# SparkFun_RTK_Facet_-_Display_SD_SIM.net
KiCad netlist of a schematic drawn in EAGLE
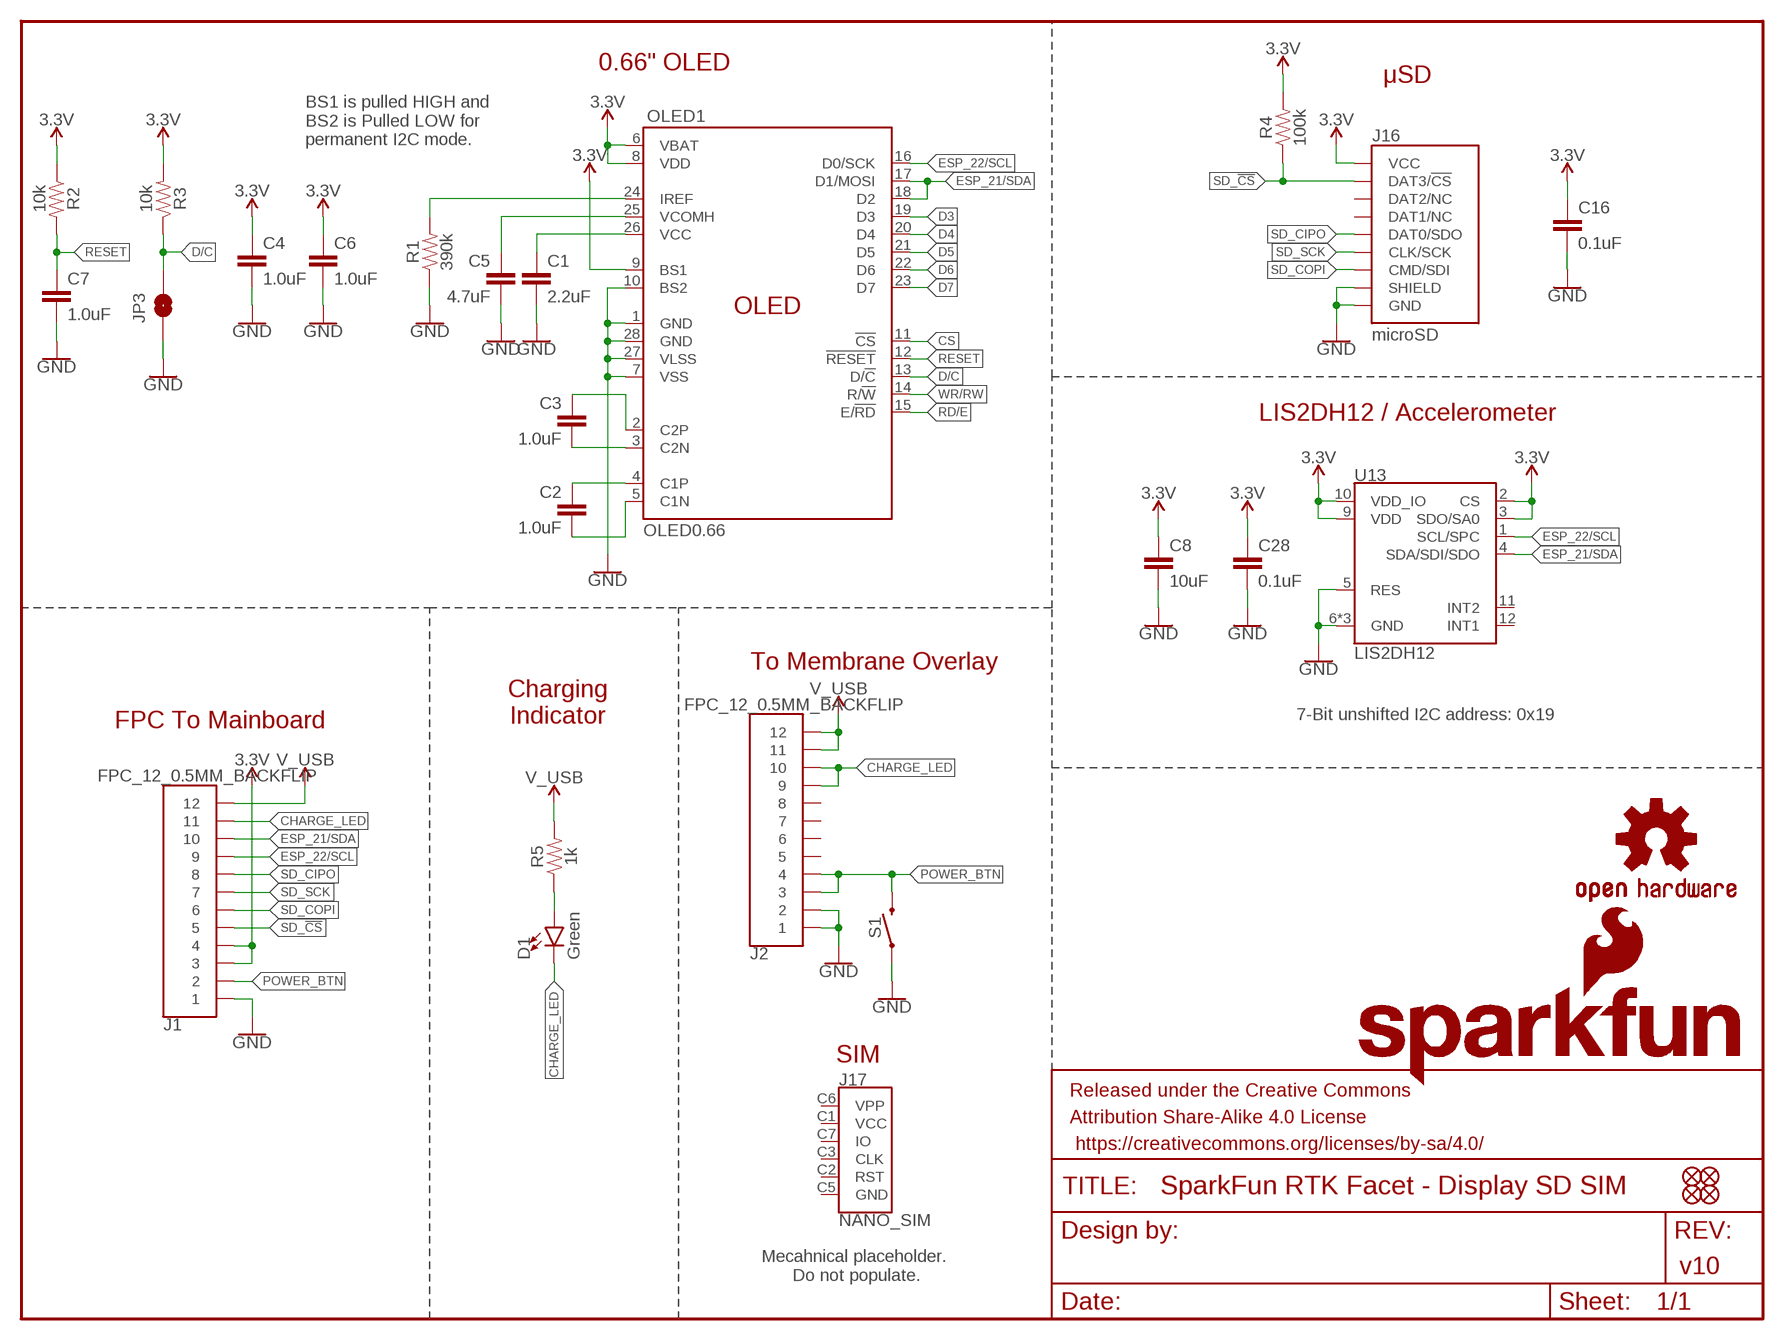
[diagram p0: schematic, sheet 1]

(export (version "E")
  (design (tool "Eeschema 10.0.6"))
  (components
    (comp (ref "C1")
      (value "2.2uF")
      (footprint "eagle-import:0805")
      (libsource (lib "eagle-import") (part "2.2UF-0805-25V-(+80/-20%)"))
    )
    (comp (ref "C2")
      (value "1.0uF")
      (footprint "eagle-import:0805")
      (libsource (lib "eagle-import") (part "1.0UF-0805-25V-10%"))
    )
    (comp (ref "C3")
      (value "1.0uF")
      (footprint "eagle-import:0805")
      (libsource (lib "eagle-import") (part "1.0UF-0805-25V-10%"))
    )
    (comp (ref "C4")
      (value "1.0uF")
      (footprint "eagle-import:0603")
      (libsource (lib "eagle-import") (part "1.0UF-0603-16V-10%"))
    )
    (comp (ref "C5")
      (value "4.7uF")
      (footprint "eagle-import:1206")
      (libsource (lib "eagle-import") (part "4.7UF-1206-16V-(+80/-20%)"))
    )
    (comp (ref "C6")
      (value "1.0uF")
      (footprint "eagle-import:0603")
      (libsource (lib "eagle-import") (part "1.0UF-0603-16V-10%"))
    )
    (comp (ref "C7")
      (value "1.0uF")
      (footprint "eagle-import:0603")
      (libsource (lib "eagle-import") (part "1.0UF-0603-16V-10%"))
    )
    (comp (ref "C8")
      (value "10uF")
      (footprint "eagle-import:0603")
      (libsource (lib "eagle-import") (part "10UF-0603-6.3V-20%"))
    )
    (comp (ref "C16")
      (value "0.1uF")
      (footprint "eagle-import:0603")
      (libsource (lib "eagle-import") (part "0.1UF-0603-25V-(+80/-20%)"))
    )
    (comp (ref "C28")
      (value "0.1uF")
      (footprint "eagle-import:0603")
      (libsource (lib "eagle-import") (part "0.1UF-0603-25V-(+80/-20%)"))
    )
    (comp (ref "D1")
      (value "Green")
      (footprint "eagle-import:LED-1206-BOTTOM")
      (libsource (lib "eagle-import") (part "LED-GREEN1206-BOTTOM"))
    )
    (comp (ref "FID1")
      (value "FIDUCIAL1X2")
      (footprint "eagle-import:FIDUCIAL-1X2")
      (libsource (lib "eagle-import") (part "FIDUCIAL1X2"))
    )
    (comp (ref "FID2")
      (value "FIDUCIAL1X2")
      (footprint "eagle-import:FIDUCIAL-1X2")
      (libsource (lib "eagle-import") (part "FIDUCIAL1X2"))
    )
    (comp (ref "FID3")
      (value "FIDUCIAL1X2")
      (footprint "eagle-import:FIDUCIAL-1X2")
      (libsource (lib "eagle-import") (part "FIDUCIAL1X2"))
    )
    (comp (ref "FID4")
      (value "FIDUCIAL1X2")
      (footprint "eagle-import:FIDUCIAL-1X2")
      (libsource (lib "eagle-import") (part "FIDUCIAL1X2"))
    )
    (comp (ref "FRAME1")
      (value "FRAME-LETTER")
      (footprint "eagle-import:CREATIVE_COMMONS")
      (libsource (lib "eagle-import") (part "FRAME-LETTER"))
    )
    (comp (ref "J1")
      (value "FPC_12_0.5MM_BACKFLIP")
      (footprint "eagle-import:FPC_12_DOUBLESIDED_BACKFLIP")
      (libsource (lib "eagle-import") (part "FPC_12_0.5MM_BACKFLIP"))
    )
    (comp (ref "J2")
      (value "FPC_12_0.5MM_BACKFLIP")
      (footprint "eagle-import:FPC_12_DOUBLESIDED_BACKFLIP")
      (libsource (lib "eagle-import") (part "FPC_12_0.5MM_BACKFLIP"))
    )
    (comp (ref "J16")
      (value "microSD")
      (footprint "eagle-import:MICRO-SD-SOCKET")
      (libsource (lib "eagle-import") (part "MICRO-SD-SDIOPUSH-PUSH"))
    )
    (comp (ref "J17")
      (value "NANO_SIM")
      (footprint "eagle-import:NANO_SIM_WURTH_693043020611")
      (libsource (lib "eagle-import") (part "NANO_SIMWURTH"))
    )
    (comp (ref "JP3")
      (value "JUMPER-SMT_2_NO_SILK")
      (footprint "eagle-import:SMT-JUMPER_2_NO_SILK")
      (libsource (lib "eagle-import") (part "JUMPER-SMT_2_NO_SILK"))
    )
    (comp (ref "LOGO3")
      (value "OSHW-LOGOMINI")
      (footprint "eagle-import:OSHW-LOGO-MINI")
      (libsource (lib "eagle-import") (part "OSHW-LOGOMINI"))
    )
    (comp (ref "LOGO5")
      (value "SFE_LOGO_NAME_FLAME.1_INCH")
      (footprint "eagle-import:SFE_LOGO_NAME_FLAME_.1")
      (libsource (lib "eagle-import") (part "SFE_LOGO_NAME_FLAME.1_INCH"))
    )
    (comp (ref "OLED1")
      (value "OLED0.66")
      (footprint "eagle-import:OLED-0.66-64X48")
      (libsource (lib "eagle-import") (part "OLED0.66"))
    )
    (comp (ref "R1")
      (value "390k")
      (footprint "eagle-import:0603")
      (libsource (lib "eagle-import") (part "390KOHM-0603-1/10W-1%"))
    )
    (comp (ref "R2")
      (value "10k")
      (footprint "eagle-import:0603")
      (libsource (lib "eagle-import") (part "10KOHM-0603-1/10W-1%"))
    )
    (comp (ref "R3")
      (value "10k")
      (footprint "eagle-import:0603")
      (libsource (lib "eagle-import") (part "10KOHM-0603-1/10W-1%"))
    )
    (comp (ref "R4")
      (value "100k")
      (footprint "eagle-import:0603")
      (libsource (lib "eagle-import") (part "100KOHM-0603-1/10W-1%"))
    )
    (comp (ref "R5")
      (value "1k")
      (footprint "eagle-import:0603")
      (libsource (lib "eagle-import") (part "1KOHM-0603-1/10W-1%"))
    )
    (comp (ref "S1")
      (value "MOMENTARY-SWITCH-SPST-SMD-5.2MM-TALL")
      (footprint "eagle-import:TACTILE_SWITCH_SMD_5.2MM")
      (libsource (lib "eagle-import") (part "MOMENTARY-SWITCH-SPST-SMD-5.2MM-TALL"))
    )
    (comp (ref "U13")
      (value "LIS2DH12")
      (footprint "eagle-import:LGA-12-LISDH12")
      (libsource (lib "eagle-import") (part "LIS2DH12"))
    )
  )
  (nets
    (net (code "1") (name "/SD_~{CS}") (class "Default")
      (node (ref "J1") (pin "5") (pinfunction "5_5") (pintype "bidirectional"))
      (node (ref "J16") (pin "CS/DAT3") (pinfunction "DAT3/~{CS}_CS/DAT3") (pintype "bidirectional"))
      (node (ref "R4") (pin "1") (pinfunction "1_1") (pintype "passive"))
    )
    (net (code "2") (name "3.3V") (class "Default")
      (node (ref "C16") (pin "1") (pinfunction "1_1") (pintype "passive"))
      (node (ref "C28") (pin "1") (pinfunction "1_1") (pintype "passive"))
      (node (ref "C4") (pin "1") (pinfunction "1_1") (pintype "passive"))
      (node (ref "C6") (pin "1") (pinfunction "1_1") (pintype "passive"))
      (node (ref "C8") (pin "1") (pinfunction "1_1") (pintype "passive"))
      (node (ref "J1") (pin "3") (pinfunction "3_3") (pintype "bidirectional"))
      (node (ref "J1") (pin "4") (pinfunction "4_4") (pintype "bidirectional"))
      (node (ref "J16") (pin "VCC") (pinfunction "VCC_VCC") (pintype "bidirectional"))
      (node (ref "OLED1") (pin "6") (pinfunction "VBAT_6") (pintype "bidirectional"))
      (node (ref "OLED1") (pin "8") (pinfunction "VDD_8") (pintype "bidirectional"))
      (node (ref "OLED1") (pin "9") (pinfunction "BS1_9") (pintype "bidirectional"))
      (node (ref "R2") (pin "1") (pinfunction "1_1") (pintype "passive"))
      (node (ref "R3") (pin "2") (pinfunction "2_2") (pintype "passive"))
      (node (ref "R4") (pin "2") (pinfunction "2_2") (pintype "passive"))
      (node (ref "U13") (pin "10") (pinfunction "VDD_IO_10") (pintype "bidirectional"))
      (node (ref "U13") (pin "2") (pinfunction "CS_2") (pintype "bidirectional"))
      (node (ref "U13") (pin "3") (pinfunction "SDO/SA0_3") (pintype "bidirectional"))
      (node (ref "U13") (pin "9") (pinfunction "VDD_9") (pintype "bidirectional"))
    )
    (net (code "3") (name "CHARGE_LED") (class "Default")
      (node (ref "D1") (pin "C") (pinfunction "C_C") (pintype "passive"))
      (node (ref "J1") (pin "11") (pinfunction "11_11") (pintype "bidirectional"))
      (node (ref "J2") (pin "10") (pinfunction "10_10") (pintype "bidirectional"))
      (node (ref "J2") (pin "9") (pinfunction "9_9") (pintype "bidirectional"))
    )
    (net (code "4") (name "CS") (class "Default")
      (node (ref "OLED1") (pin "11") (pinfunction "~{CS}_11") (pintype "bidirectional"))
    )
    (net (code "5") (name "D3") (class "Default")
      (node (ref "OLED1") (pin "19") (pinfunction "D3_19") (pintype "bidirectional"))
    )
    (net (code "6") (name "D4") (class "Default")
      (node (ref "OLED1") (pin "20") (pinfunction "D4_20") (pintype "bidirectional"))
    )
    (net (code "7") (name "D5") (class "Default")
      (node (ref "OLED1") (pin "21") (pinfunction "D5_21") (pintype "bidirectional"))
    )
    (net (code "8") (name "D6") (class "Default")
      (node (ref "OLED1") (pin "22") (pinfunction "D6_22") (pintype "bidirectional"))
    )
    (net (code "9") (name "D7") (class "Default")
      (node (ref "OLED1") (pin "23") (pinfunction "D7_23") (pintype "bidirectional"))
    )
    (net (code "10") (name "D{slash}C") (class "Default")
      (node (ref "JP3") (pin "2") (pinfunction "2_2") (pintype "passive"))
      (node (ref "OLED1") (pin "13") (pinfunction "D/~{C}_13") (pintype "bidirectional"))
      (node (ref "R3") (pin "1") (pinfunction "1_1") (pintype "passive"))
    )
    (net (code "11") (name "ESP_21{slash}SDA") (class "Default")
      (node (ref "J1") (pin "10") (pinfunction "10_10") (pintype "bidirectional"))
      (node (ref "OLED1") (pin "17") (pinfunction "D1/MOSI_17") (pintype "bidirectional"))
      (node (ref "OLED1") (pin "18") (pinfunction "D2_18") (pintype "bidirectional"))
      (node (ref "U13") (pin "4") (pinfunction "SDA/SDI/SDO_4") (pintype "bidirectional"))
    )
    (net (code "12") (name "ESP_22{slash}SCL") (class "Default")
      (node (ref "J1") (pin "9") (pinfunction "9_9") (pintype "bidirectional"))
      (node (ref "OLED1") (pin "16") (pinfunction "D0/SCK_16") (pintype "bidirectional"))
      (node (ref "U13") (pin "1") (pinfunction "SCL/SPC_1") (pintype "bidirectional"))
    )
    (net (code "13") (name "GND") (class "Default")
      (node (ref "C1") (pin "2") (pinfunction "2_2") (pintype "passive"))
      (node (ref "C16") (pin "2") (pinfunction "2_2") (pintype "passive"))
      (node (ref "C28") (pin "2") (pinfunction "2_2") (pintype "passive"))
      (node (ref "C4") (pin "2") (pinfunction "2_2") (pintype "passive"))
      (node (ref "C5") (pin "2") (pinfunction "2_2") (pintype "passive"))
      (node (ref "C6") (pin "2") (pinfunction "2_2") (pintype "passive"))
      (node (ref "C7") (pin "2") (pinfunction "2_2") (pintype "passive"))
      (node (ref "C8") (pin "2") (pinfunction "2_2") (pintype "passive"))
      (node (ref "J1") (pin "1") (pinfunction "1_1") (pintype "bidirectional"))
      (node (ref "J16") (pin "CD1") (pinfunction "SHIELD_CD1") (pintype "bidirectional"))
      (node (ref "J16") (pin "GND") (pinfunction "GND_GND") (pintype "bidirectional"))
      (node (ref "J16") (pin "GND1") (pinfunction "GND_GND1") (pintype "bidirectional"))
      (node (ref "J16") (pin "GND3") (pinfunction "GND_GND3") (pintype "bidirectional"))
      (node (ref "J2") (pin "1") (pinfunction "1_1") (pintype "bidirectional"))
      (node (ref "J2") (pin "2") (pinfunction "2_2") (pintype "bidirectional"))
      (node (ref "JP3") (pin "1") (pinfunction "1_1") (pintype "passive"))
      (node (ref "OLED1") (pin "1") (pinfunction "GND_1") (pintype "bidirectional"))
      (node (ref "OLED1") (pin "10") (pinfunction "BS2_10") (pintype "bidirectional"))
      (node (ref "OLED1") (pin "27") (pinfunction "VLSS_27") (pintype "bidirectional"))
      (node (ref "OLED1") (pin "28") (pinfunction "GND_28") (pintype "bidirectional"))
      (node (ref "OLED1") (pin "7") (pinfunction "VSS_7") (pintype "bidirectional"))
      (node (ref "R1") (pin "1") (pinfunction "1_1") (pintype "passive"))
      (node (ref "S1") (pin "1") (pinfunction "1_1") (pintype "passive"))
      (node (ref "U13") (pin "5") (pinfunction "RES_5") (pintype "bidirectional"))
      (node (ref "U13") (pin "6") (pinfunction "GND_6") (pintype "bidirectional"))
      (node (ref "U13") (pin "7") (pinfunction "GND_7") (pintype "bidirectional"))
      (node (ref "U13") (pin "8") (pinfunction "GND_8") (pintype "bidirectional"))
    )
    (net (code "14") (name "Net-(D1-PadA)") (class "Default")
      (node (ref "D1") (pin "A") (pinfunction "A_A") (pintype "passive"))
      (node (ref "R5") (pin "1") (pinfunction "1_1") (pintype "passive"))
    )
    (net (code "15") (name "Net-(OLED1-C1N)") (class "Default")
      (node (ref "C2") (pin "2") (pinfunction "2_2") (pintype "passive"))
      (node (ref "OLED1") (pin "5") (pinfunction "C1N_5") (pintype "bidirectional"))
    )
    (net (code "16") (name "Net-(OLED1-C1P)") (class "Default")
      (node (ref "C2") (pin "1") (pinfunction "1_1") (pintype "passive"))
      (node (ref "OLED1") (pin "4") (pinfunction "C1P_4") (pintype "bidirectional"))
    )
    (net (code "17") (name "Net-(OLED1-C2N)") (class "Default")
      (node (ref "C3") (pin "2") (pinfunction "2_2") (pintype "passive"))
      (node (ref "OLED1") (pin "3") (pinfunction "C2N_3") (pintype "bidirectional"))
    )
    (net (code "18") (name "Net-(OLED1-C2P)") (class "Default")
      (node (ref "C3") (pin "1") (pinfunction "1_1") (pintype "passive"))
      (node (ref "OLED1") (pin "2") (pinfunction "C2P_2") (pintype "bidirectional"))
    )
    (net (code "19") (name "Net-(OLED1-IREF)") (class "Default")
      (node (ref "OLED1") (pin "24") (pinfunction "IREF_24") (pintype "bidirectional"))
      (node (ref "R1") (pin "2") (pinfunction "2_2") (pintype "passive"))
    )
    (net (code "20") (name "Net-(OLED1-VCC)") (class "Default")
      (node (ref "C1") (pin "1") (pinfunction "1_1") (pintype "passive"))
      (node (ref "OLED1") (pin "26") (pinfunction "VCC_26") (pintype "bidirectional"))
    )
    (net (code "21") (name "Net-(OLED1-VCOMH)") (class "Default")
      (node (ref "C5") (pin "1") (pinfunction "1_1") (pintype "passive"))
      (node (ref "OLED1") (pin "25") (pinfunction "VCOMH_25") (pintype "bidirectional"))
    )
    (net (code "22") (name "POWER_BTN") (class "Default")
      (node (ref "J1") (pin "2") (pinfunction "2_2") (pintype "bidirectional"))
      (node (ref "J2") (pin "3") (pinfunction "3_3") (pintype "bidirectional"))
      (node (ref "J2") (pin "4") (pinfunction "4_4") (pintype "bidirectional"))
      (node (ref "S1") (pin "3") (pinfunction "2_3") (pintype "passive"))
    )
    (net (code "23") (name "RD{slash}E") (class "Default")
      (node (ref "OLED1") (pin "15") (pinfunction "E/~{RD}_15") (pintype "bidirectional"))
    )
    (net (code "24") (name "RESET") (class "Default")
      (node (ref "C7") (pin "1") (pinfunction "1_1") (pintype "passive"))
      (node (ref "OLED1") (pin "12") (pinfunction "~{RESET}_12") (pintype "bidirectional"))
      (node (ref "R2") (pin "2") (pinfunction "2_2") (pintype "passive"))
    )
    (net (code "25") (name "SD_CIPO") (class "Default")
      (node (ref "J1") (pin "8") (pinfunction "8_8") (pintype "bidirectional"))
      (node (ref "J16") (pin "DO/DAT0") (pinfunction "DAT0/SDO_DO/DAT0") (pintype "bidirectional"))
    )
    (net (code "26") (name "SD_COPI") (class "Default")
      (node (ref "J1") (pin "6") (pinfunction "6_6") (pintype "bidirectional"))
      (node (ref "J16") (pin "DI/CMD") (pinfunction "CMD/SDI_DI/CMD") (pintype "bidirectional"))
    )
    (net (code "27") (name "SD_SCK") (class "Default")
      (node (ref "J1") (pin "7") (pinfunction "7_7") (pintype "bidirectional"))
      (node (ref "J16") (pin "SCLK") (pinfunction "CLK/SCK_SCLK") (pintype "bidirectional"))
    )
    (net (code "28") (name "V_USB") (class "Default")
      (node (ref "J1") (pin "12") (pinfunction "12_12") (pintype "bidirectional"))
      (node (ref "J2") (pin "11") (pinfunction "11_11") (pintype "bidirectional"))
      (node (ref "J2") (pin "12") (pinfunction "12_12") (pintype "bidirectional"))
      (node (ref "R5") (pin "2") (pinfunction "2_2") (pintype "passive"))
    )
    (net (code "29") (name "WR{slash}RW") (class "Default")
      (node (ref "OLED1") (pin "14") (pinfunction "R/~{W}_14") (pintype "bidirectional"))
    )
    (net (code "30") (name "unconnected-(J2-Pad5)") (class "Default")
      (node (ref "J2") (pin "5") (pinfunction "5_5") (pintype "bidirectional"))
    )
    (net (code "31") (name "unconnected-(J2-Pad6)") (class "Default")
      (node (ref "J2") (pin "6") (pinfunction "6_6") (pintype "bidirectional"))
    )
    (net (code "32") (name "unconnected-(J2-Pad7)") (class "Default")
      (node (ref "J2") (pin "7") (pinfunction "7_7") (pintype "bidirectional"))
    )
    (net (code "33") (name "unconnected-(J2-Pad8)") (class "Default")
      (node (ref "J2") (pin "8") (pinfunction "8_8") (pintype "bidirectional"))
    )
    (net (code "34") (name "unconnected-(J16-DAT1{slash}NC-PadDAT1)") (class "Default")
      (node (ref "J16") (pin "DAT1") (pinfunction "DAT1/NC_DAT1") (pintype "bidirectional"))
    )
    (net (code "35") (name "unconnected-(J16-DAT2{slash}NC-PadDAT2)") (class "Default")
      (node (ref "J16") (pin "DAT2") (pinfunction "DAT2/NC_DAT2") (pintype "bidirectional"))
    )
    (net (code "36") (name "unconnected-(J17-CLK-PadC3)") (class "Default")
      (node (ref "J17") (pin "C3") (pinfunction "CLK_C3") (pintype "bidirectional"))
    )
    (net (code "37") (name "unconnected-(J17-GND-PadC5)") (class "Default")
      (node (ref "J17") (pin "C5") (pinfunction "GND_C5") (pintype "bidirectional"))
    )
    (net (code "38") (name "unconnected-(J17-IO-PadC7)") (class "Default")
      (node (ref "J17") (pin "C7") (pinfunction "IO_C7") (pintype "bidirectional"))
    )
    (net (code "39") (name "unconnected-(J17-RST-PadC2)") (class "Default")
      (node (ref "J17") (pin "C2") (pinfunction "RST_C2") (pintype "bidirectional"))
    )
    (net (code "40") (name "unconnected-(J17-VCC-PadC1)") (class "Default")
      (node (ref "J17") (pin "C1") (pinfunction "VCC_C1") (pintype "bidirectional"))
    )
    (net (code "41") (name "unconnected-(J17-VPP-PadC6)") (class "Default")
      (node (ref "J17") (pin "C6") (pinfunction "VPP_C6") (pintype "bidirectional"))
    )
    (net (code "42") (name "unconnected-(U13-INT1-Pad12)") (class "Default")
      (node (ref "U13") (pin "12") (pinfunction "INT1_12") (pintype "bidirectional"))
    )
    (net (code "43") (name "unconnected-(U13-INT2-Pad11)") (class "Default")
      (node (ref "U13") (pin "11") (pinfunction "INT2_11") (pintype "bidirectional"))
    )
  )
)
